# pt_100__2.net
KiCad netlist of a schematic drawn in EAGLE
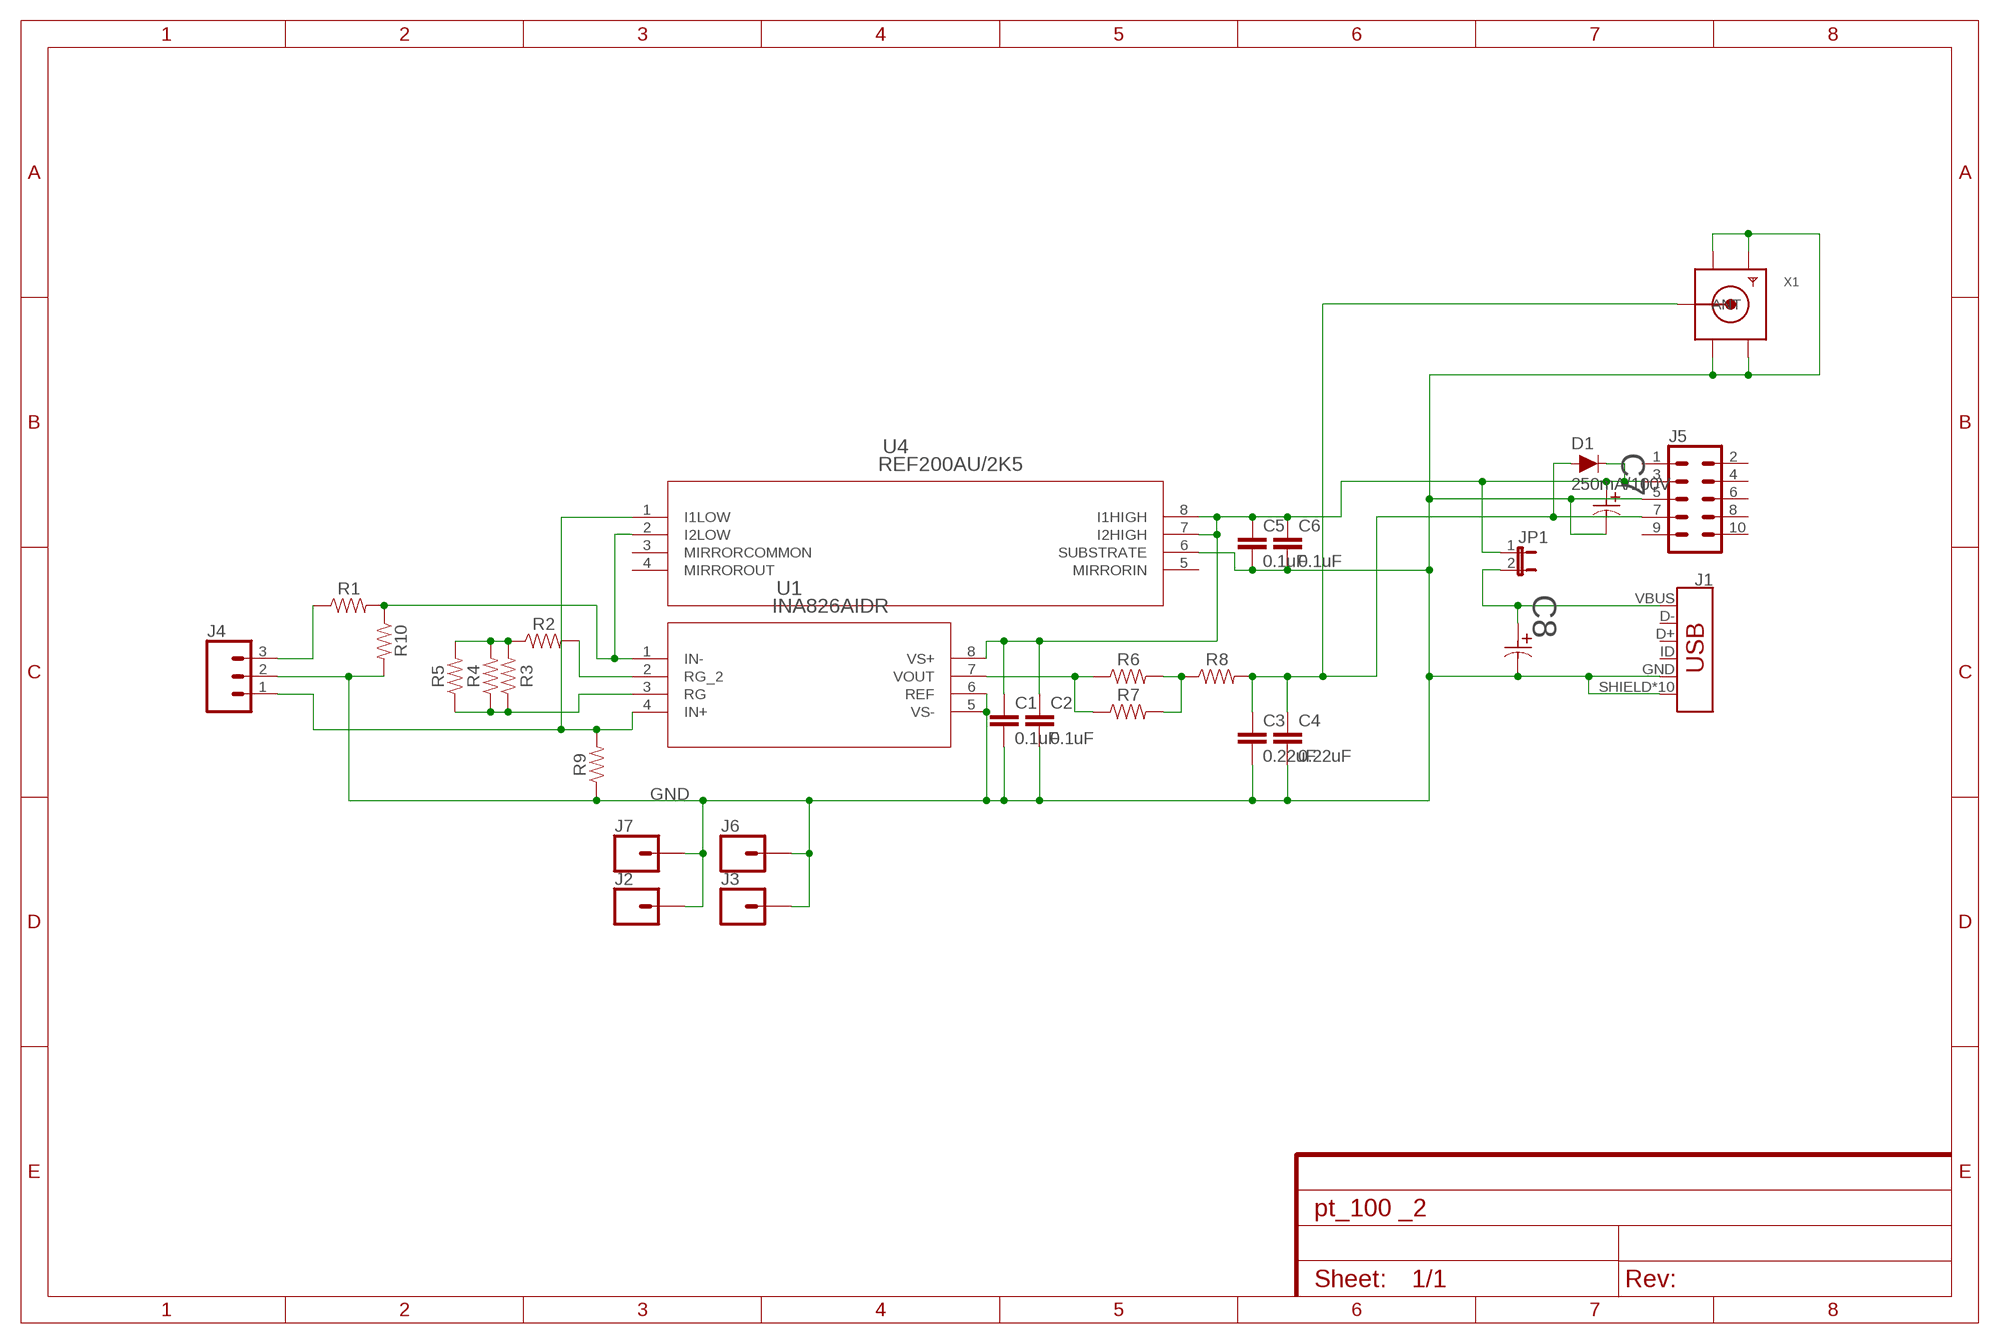
[diagram p0: schematic, sheet 1]

(export (version "E")
  (design (tool "Eeschema 10.0.6"))
  (components
    (comp (ref "C1")
      (value "0.1uF")
      (footprint "eagle-import:0402")
      (libsource (lib "eagle-import") (part "0.1UF-0402-6.3V-10%-X7R"))
    )
    (comp (ref "C2")
      (value "0.1uF")
      (footprint "eagle-import:0402")
      (fields (field (name "SPICEPREFIX") "C"))
      (libsource (lib "eagle-import") (part "0.1UF-0402-6.3V-10%-X7R"))
    )
    (comp (ref "C3")
      (value "0.22uF")
      (footprint "eagle-import:0402")
      (libsource (lib "eagle-import") (part "0.1UF-0402-6.3V-10%-X7R"))
    )
    (comp (ref "C4")
      (value "0.22uF")
      (footprint "eagle-import:0402")
      (libsource (lib "eagle-import") (part "0.1UF-0402-6.3V-10%-X7R"))
    )
    (comp (ref "C5")
      (value "0.1uF")
      (footprint "eagle-import:0402")
      (libsource (lib "eagle-import") (part "0.1UF-0402-6.3V-10%-X7R"))
    )
    (comp (ref "C6")
      (value "0.1uF")
      (footprint "eagle-import:0402")
      (libsource (lib "eagle-import") (part "0.1UF-0402-6.3V-10%-X7R"))
    )
    (comp (ref "C7")
      (value "T491D106K025AT")
      (footprint "eagle-import:CAPMP7.6X4.3_3.1N_KEM")
      (libsource (lib "eagle-import") (part "T491D106K025AT"))
    )
    (comp (ref "C8")
      (value "T491D106K025AT")
      (footprint "eagle-import:CAPMP7.6X4.3_3.1N_KEM")
      (libsource (lib "eagle-import") (part "T491D106K025AT"))
    )
    (comp (ref "D1")
      (value "250mA/100V")
      (footprint "eagle-import:SOD-323")
      (libsource (lib "eagle-import") (part "DIODE-BAS16J"))
    )
    (comp (ref "J1")
      (value "USB_MICRO-B_HALF_PTH_MILL")
      (footprint "eagle-import:USB-MICROB-PTH-MILL")
      (libsource (lib "eagle-import") (part "USB_MICRO-B_HALF_PTH_MILL"))
    )
    (comp (ref "J2")
      (value "CONN_01")
      (footprint "eagle-import:1X01")
      (libsource (lib "eagle-import") (part "CONN_01"))
    )
    (comp (ref "J3")
      (value "CONN_01")
      (footprint "eagle-import:1X01")
      (libsource (lib "eagle-import") (part "CONN_01"))
    )
    (comp (ref "J4")
      (value "CONN_03-SCREW-5MM")
      (footprint "eagle-import:SCREWTERMINAL-5MM-3")
      (libsource (lib "eagle-import") (part "CONN_03-SCREW-5MM"))
    )
    (comp (ref "J5")
      (value "CONN_05X2SHD_LOCK")
      (footprint "eagle-import:2X5-SHROUDED_LOCK")
      (libsource (lib "eagle-import") (part "CONN_05X2SHD_LOCK"))
    )
    (comp (ref "J6")
      (value "CONN_01")
      (footprint "eagle-import:1X01")
      (libsource (lib "eagle-import") (part "CONN_01"))
    )
    (comp (ref "J7")
      (value "CONN_01")
      (footprint "eagle-import:1X01")
      (libsource (lib "eagle-import") (part "CONN_01"))
    )
    (comp (ref "JP1")
      (value "JUMPER-2PTH")
      (footprint "eagle-import:1X02")
      (libsource (lib "eagle-import") (part "JUMPER-2PTH"))
    )
    (comp (ref "R1")
      (value "82")
      (footprint "eagle-import:0402")
      (libsource (lib "eagle-import") (part "1KOHM-0402-1/16W-1%"))
    )
    (comp (ref "R2")
      (value "0")
      (footprint "eagle-import:0402")
      (libsource (lib "eagle-import") (part "1KOHM-0402-1/16W-1%"))
    )
    (comp (ref "R3")
      (value "75")
      (footprint "eagle-import:0402")
      (libsource (lib "eagle-import") (part "1KOHM-0402-1/16W-1%"))
    )
    (comp (ref "R4")
      (value "75")
      (footprint "eagle-import:0402")
      (libsource (lib "eagle-import") (part "1KOHM-0402-1/16W-1%"))
    )
    (comp (ref "R5")
      (value "75")
      (footprint "eagle-import:0402")
      (libsource (lib "eagle-import") (part "1KOHM-0402-1/16W-1%"))
    )
    (comp (ref "R6")
      (value "75")
      (footprint "eagle-import:0402")
      (libsource (lib "eagle-import") (part "1KOHM-0402-1/16W-1%"))
    )
    (comp (ref "R7")
      (value "1KOHM-0402-1/16W-1%")
      (footprint "eagle-import:0402")
      (libsource (lib "eagle-import") (part "1KOHM-0402-1/16W-1%"))
    )
    (comp (ref "R8")
      (value "0")
      (footprint "eagle-import:0402")
      (libsource (lib "eagle-import") (part "1KOHM-0402-1/16W-1%"))
    )
    (comp (ref "R9")
      (value "1KOHM-0402-1/16W-1%")
      (footprint "eagle-import:0402")
      (libsource (lib "eagle-import") (part "1KOHM-0402-1/16W-1%"))
    )
    (comp (ref "R10")
      (value "1KOHM-0402-1/16W-1%")
      (footprint "eagle-import:0402")
      (libsource (lib "eagle-import") (part "1KOHM-0402-1/16W-1%"))
    )
    (comp (ref "U1")
      (value "INA826AIDR")
      (footprint "eagle-import:D8")
      (fields (field (name "GENERIC_PART_NUMBER") "INA826") (field (name "MANUFACTURER") "Texas Instruments"))
      (libsource (lib "eagle-import") (part "INA826AIDR"))
    )
    (comp (ref "U4")
      (value "REF200AU/2K5")
      (footprint "eagle-import:D8")
      (fields (field (name "GENERIC_PART_NUMBER") "REF200") (field (name "MANUFACTURER") "Texas Instruments"))
      (libsource (lib "eagle-import") (part "REF200AU/2K5"))
    )
    (comp (ref "X1")
      (value "SMACONNECTOR_EDGE")
      (footprint "eagle-import:SMA_EDGELAUNCH")
      (libsource (lib "eagle-import") (part "SMACONNECTOR_EDGE"))
    )
  )
  (nets
    (net (code "1") (name "/GND") (class "Default")
      (node (ref "C1") (pin "2") (pinfunction "2_2") (pintype "passive"))
      (node (ref "C2") (pin "2") (pinfunction "2_2") (pintype "passive"))
      (node (ref "C3") (pin "2") (pinfunction "2_2") (pintype "passive"))
      (node (ref "C4") (pin "2") (pinfunction "2_2") (pintype "passive"))
      (node (ref "C5") (pin "2") (pinfunction "2_2") (pintype "passive"))
      (node (ref "C6") (pin "2") (pinfunction "2_2") (pintype "passive"))
      (node (ref "C7") (pin "2") (pinfunction "2_2") (pintype "passive"))
      (node (ref "C8") (pin "2") (pinfunction "2_2") (pintype "passive"))
      (node (ref "J1") (pin "GND") (pinfunction "GND_GND") (pintype "power_in"))
      (node (ref "J1") (pin "SHIELD") (pinfunction "SHIELD_SHIELD") (pintype "bidirectional"))
      (node (ref "J1") (pin "SHIELD10") (pinfunction "SHIELD_SHIELD10") (pintype "bidirectional"))
      (node (ref "J1") (pin "SHIELD2") (pinfunction "SHIELD_SHIELD2") (pintype "bidirectional"))
      (node (ref "J1") (pin "SHIELD3") (pinfunction "SHIELD_SHIELD3") (pintype "bidirectional"))
      (node (ref "J1") (pin "SHIELD4") (pinfunction "SHIELD_SHIELD4") (pintype "bidirectional"))
      (node (ref "J1") (pin "SHIELD5") (pinfunction "SHIELD_SHIELD5") (pintype "bidirectional"))
      (node (ref "J1") (pin "SHIELD6") (pinfunction "SHIELD_SHIELD6") (pintype "bidirectional"))
      (node (ref "J1") (pin "SHIELD7") (pinfunction "SHIELD_SHIELD7") (pintype "bidirectional"))
      (node (ref "J1") (pin "SHIELD8") (pinfunction "SHIELD_SHIELD8") (pintype "bidirectional"))
      (node (ref "J1") (pin "SHIELD9") (pinfunction "SHIELD_SHIELD9") (pintype "bidirectional"))
      (node (ref "J2") (pin "1") (pinfunction "1_1") (pintype "passive"))
      (node (ref "J3") (pin "1") (pinfunction "1_1") (pintype "passive"))
      (node (ref "J4") (pin "2") (pinfunction "2_2") (pintype "passive"))
      (node (ref "J5") (pin "5") (pinfunction "5_5") (pintype "passive"))
      (node (ref "J6") (pin "1") (pinfunction "1_1") (pintype "passive"))
      (node (ref "J7") (pin "1") (pinfunction "1_1") (pintype "passive"))
      (node (ref "R10") (pin "2") (pinfunction "2_2") (pintype "passive"))
      (node (ref "R9") (pin "1") (pinfunction "1_1") (pintype "passive"))
      (node (ref "U1") (pin "5") (pinfunction "VS-_5") (pintype "power_in"))
      (node (ref "U1") (pin "6") (pinfunction "REF_6") (pintype "passive"))
      (node (ref "U4") (pin "6") (pinfunction "SUBSTRATE_6") (pintype "passive"))
      (node (ref "X1") (pin "GND@1") (pinfunction "GND4_GND@1") (pintype "power_in"))
      (node (ref "X1") (pin "GND@2") (pinfunction "GND3_GND@2") (pintype "power_in"))
      (node (ref "X1") (pin "GND@3") (pinfunction "GND2_GND@3") (pintype "power_in"))
      (node (ref "X1") (pin "GND@4") (pinfunction "GND1_GND@4") (pintype "power_in"))
    )
    (net (code "2") (name "Net-(C8-Pad1)") (class "Default")
      (node (ref "C8") (pin "1") (pinfunction "1_1") (pintype "passive"))
      (node (ref "J1") (pin "VBUS") (pinfunction "VBUS_VBUS") (pintype "power_in"))
      (node (ref "JP1") (pin "2") (pinfunction "2_2") (pintype "passive"))
    )
    (net (code "3") (name "Net-(J4-Pad3)") (class "Default")
      (node (ref "J4") (pin "3") (pinfunction "3_3") (pintype "passive"))
      (node (ref "R1") (pin "1") (pinfunction "1_1") (pintype "passive"))
    )
    (net (code "4") (name "Net-(R2-Pad1)") (class "Default")
      (node (ref "R2") (pin "1") (pinfunction "1_1") (pintype "passive"))
      (node (ref "R3") (pin "2") (pinfunction "2_2") (pintype "passive"))
      (node (ref "R4") (pin "2") (pinfunction "2_2") (pintype "passive"))
      (node (ref "R5") (pin "2") (pinfunction "2_2") (pintype "passive"))
    )
    (net (code "5") (name "Net-(R6-Pad2)") (class "Default")
      (node (ref "R6") (pin "2") (pinfunction "2_2") (pintype "passive"))
      (node (ref "R7") (pin "2") (pinfunction "2_2") (pintype "passive"))
      (node (ref "R8") (pin "1") (pinfunction "1_1") (pintype "passive"))
    )
    (net (code "6") (name "Net-(U1-IN+)") (class "Default")
      (node (ref "J4") (pin "1") (pinfunction "1_1") (pintype "passive"))
      (node (ref "R9") (pin "2") (pinfunction "2_2") (pintype "passive"))
      (node (ref "U1") (pin "4") (pinfunction "IN+_4") (pintype "input"))
      (node (ref "U4") (pin "1") (pinfunction "I1LOW_1") (pintype "passive"))
    )
    (net (code "7") (name "Net-(U1-IN-)") (class "Default")
      (node (ref "R1") (pin "2") (pinfunction "2_2") (pintype "passive"))
      (node (ref "R10") (pin "1") (pinfunction "1_1") (pintype "passive"))
      (node (ref "U1") (pin "1") (pinfunction "IN-_1") (pintype "input"))
      (node (ref "U4") (pin "2") (pinfunction "I2LOW_2") (pintype "passive"))
    )
    (net (code "8") (name "Net-(U1-RG)") (class "Default")
      (node (ref "R3") (pin "1") (pinfunction "1_1") (pintype "passive"))
      (node (ref "R4") (pin "1") (pinfunction "1_1") (pintype "passive"))
      (node (ref "R5") (pin "1") (pinfunction "1_1") (pintype "passive"))
      (node (ref "U1") (pin "3") (pinfunction "RG_3") (pintype "passive"))
    )
    (net (code "9") (name "Net-(U1-RG_2)") (class "Default")
      (node (ref "R2") (pin "2") (pinfunction "2_2") (pintype "passive"))
      (node (ref "U1") (pin "2") (pinfunction "RG_2_2") (pintype "passive"))
    )
    (net (code "10") (name "Net-(U1-VOUT)") (class "Default")
      (node (ref "R6") (pin "1") (pinfunction "1_1") (pintype "passive"))
      (node (ref "R7") (pin "1") (pinfunction "1_1") (pintype "passive"))
      (node (ref "U1") (pin "7") (pinfunction "VOUT_7") (pintype "output"))
    )
    (net (code "11") (name "Net-(U1-VS+)") (class "Default")
      (node (ref "C1") (pin "1") (pinfunction "1_1") (pintype "passive"))
      (node (ref "C2") (pin "1") (pinfunction "1_1") (pintype "passive"))
      (node (ref "C5") (pin "1") (pinfunction "1_1") (pintype "passive"))
      (node (ref "C6") (pin "1") (pinfunction "1_1") (pintype "passive"))
      (node (ref "C7") (pin "1") (pinfunction "1_1") (pintype "passive"))
      (node (ref "D1") (pin "C") (pinfunction "C_C") (pintype "passive"))
      (node (ref "J5") (pin "3") (pinfunction "3_3") (pintype "passive"))
      (node (ref "JP1") (pin "1") (pinfunction "1_1") (pintype "passive"))
      (node (ref "U1") (pin "8") (pinfunction "VS+_8") (pintype "power_in"))
      (node (ref "U4") (pin "7") (pinfunction "I2HIGH_7") (pintype "passive"))
      (node (ref "U4") (pin "8") (pinfunction "I1HIGH_8") (pintype "passive"))
    )
    (net (code "12") (name "Net-(X1-ANT)") (class "Default")
      (node (ref "C3") (pin "1") (pinfunction "1_1") (pintype "passive"))
      (node (ref "C4") (pin "1") (pinfunction "1_1") (pintype "passive"))
      (node (ref "D1") (pin "A") (pinfunction "A_A") (pintype "passive"))
      (node (ref "J5") (pin "7") (pinfunction "7_7") (pintype "passive"))
      (node (ref "R8") (pin "2") (pinfunction "2_2") (pintype "passive"))
      (node (ref "X1") (pin "P") (pinfunction "ANT_P") (pintype "bidirectional"))
    )
    (net (code "13") (name "unconnected-(J1-PadD+)") (class "Default")
      (node (ref "J1") (pin "D+") (pinfunction "D+_D+") (pintype "bidirectional"))
    )
    (net (code "14") (name "unconnected-(J1-PadD-)") (class "Default")
      (node (ref "J1") (pin "D-") (pinfunction "D-_D-") (pintype "bidirectional"))
    )
    (net (code "15") (name "unconnected-(J1-PadID)") (class "Default")
      (node (ref "J1") (pin "ID") (pinfunction "ID_ID") (pintype "bidirectional"))
    )
    (net (code "16") (name "unconnected-(J5-Pad1)") (class "Default")
      (node (ref "J5") (pin "1") (pinfunction "1_1") (pintype "passive"))
    )
    (net (code "17") (name "unconnected-(J5-Pad2)") (class "Default")
      (node (ref "J5") (pin "2") (pinfunction "2_2") (pintype "passive"))
    )
    (net (code "18") (name "unconnected-(J5-Pad4)") (class "Default")
      (node (ref "J5") (pin "4") (pinfunction "4_4") (pintype "passive"))
    )
    (net (code "19") (name "unconnected-(J5-Pad6)") (class "Default")
      (node (ref "J5") (pin "6") (pinfunction "6_6") (pintype "passive"))
    )
    (net (code "20") (name "unconnected-(J5-Pad8)") (class "Default")
      (node (ref "J5") (pin "8") (pinfunction "8_8") (pintype "passive"))
    )
    (net (code "21") (name "unconnected-(J5-Pad9)") (class "Default")
      (node (ref "J5") (pin "9") (pinfunction "9_9") (pintype "passive"))
    )
    (net (code "22") (name "unconnected-(J5-Pad10)") (class "Default")
      (node (ref "J5") (pin "10") (pinfunction "10_10") (pintype "passive"))
    )
    (net (code "23") (name "unconnected-(U4-MIRRORCOMMON-Pad3)") (class "Default")
      (node (ref "U4") (pin "3") (pinfunction "MIRRORCOMMON_3") (pintype "passive"))
    )
    (net (code "24") (name "unconnected-(U4-MIRRORIN-Pad5)") (class "Default")
      (node (ref "U4") (pin "5") (pinfunction "MIRRORIN_5") (pintype "input"))
    )
    (net (code "25") (name "unconnected-(U4-MIRROROUT-Pad4)") (class "Default")
      (node (ref "U4") (pin "4") (pinfunction "MIRROROUT_4") (pintype "output"))
    )
  )
)
